# my_ws2812.net
KiCad netlist of a schematic drawn in Altium Designer
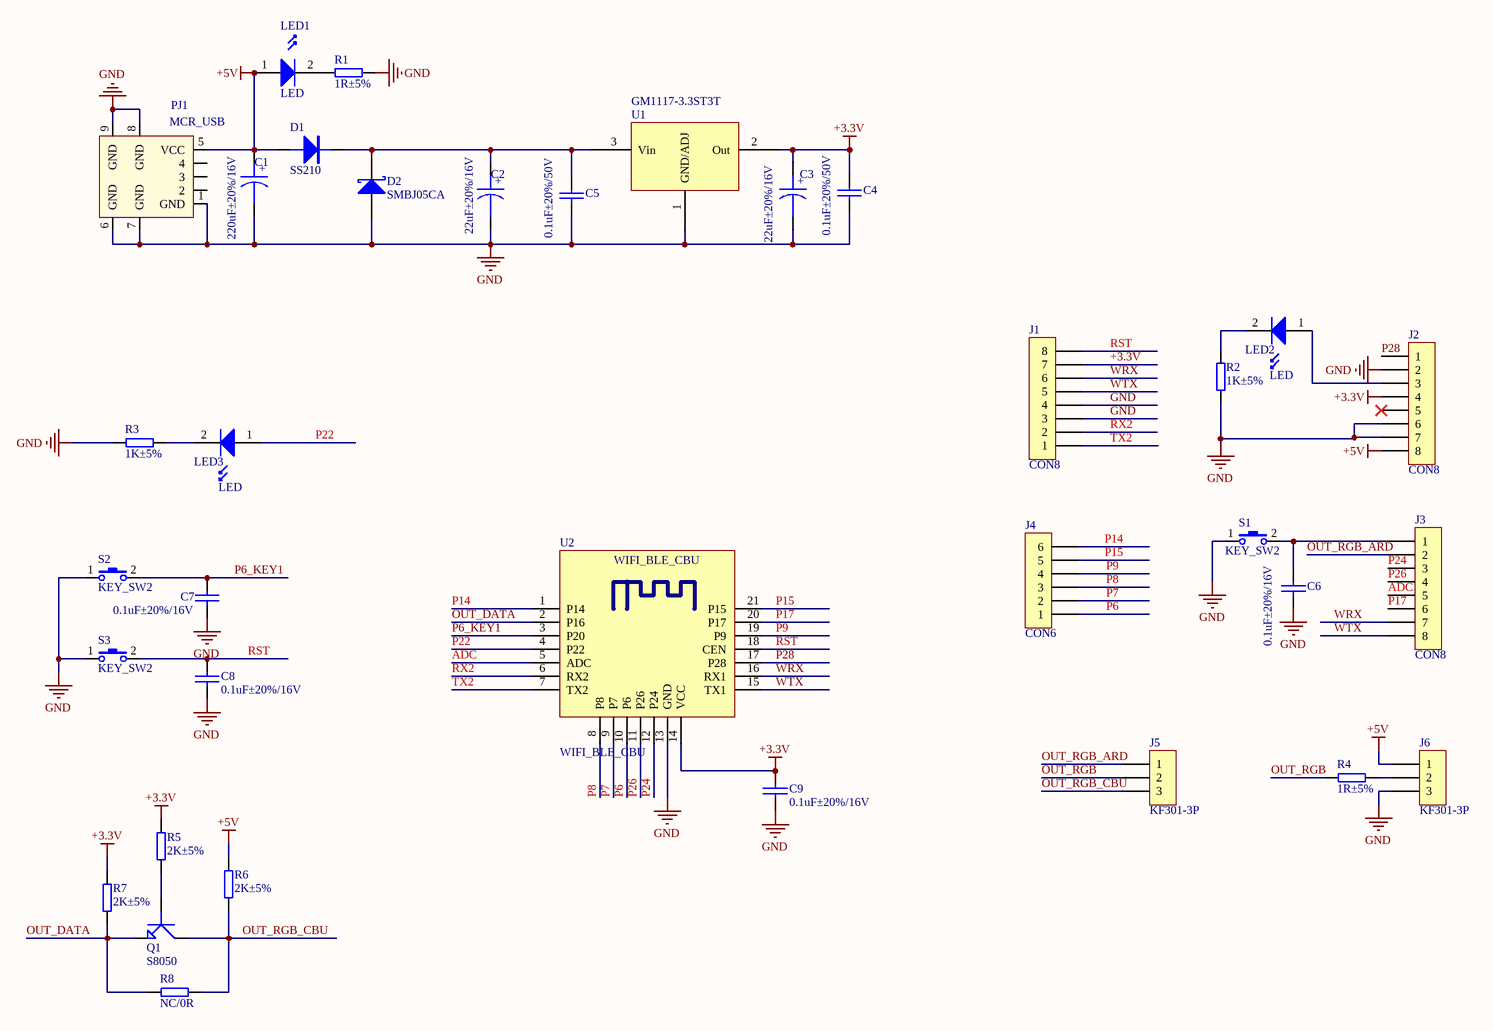
[diagram p0: my_ws2812.SchDoc]

(export (version "E")
  (design (tool "Eeschema 10.0.6"))
  (components
    (comp (ref "C1")
      (value "220uF±20%/16V")
      (footprint "CD0.15")
      (description "Capacitor")
      (libsource (lib "*") (part "CAPACITOR POL"))
    )
    (comp (ref "C2")
      (value "22uF±20%/16V")
      (footprint "钽电容B3528")
      (description "Capacitor")
      (libsource (lib "*") (part "CAPACITOR POL"))
    )
    (comp (ref "C3")
      (value "22uF±20%/16V")
      (footprint "钽电容B3528")
      (description "Capacitor")
      (libsource (lib "*") (part "CAPACITOR POL"))
    )
    (comp (ref "C4")
      (value "0.1uF±20%/50V")
      (footprint "C0603")
      (description "Capacitor")
      (libsource (lib "昊华元件库sch") (part "CAP"))
    )
    (comp (ref "C5")
      (value "0.1uF±20%/50V")
      (footprint "C0603")
      (description "Capacitor")
      (libsource (lib "昊华元件库sch") (part "CAP"))
    )
    (comp (ref "C6")
      (value "0.1uF±20%/16V")
      (footprint "C0603")
      (description "Capacitor")
      (libsource (lib "昊华元件库sch") (part "CAP"))
    )
    (comp (ref "C7")
      (value "0.1uF±20%/16V")
      (footprint "C0603")
      (description "Capacitor")
      (libsource (lib "昊华元件库sch") (part "CAP"))
    )
    (comp (ref "C8")
      (value "0.1uF±20%/16V")
      (footprint "C0603")
      (description "Capacitor")
      (libsource (lib "昊华元件库sch") (part "CAP"))
    )
    (comp (ref "C9")
      (value "0.1uF±20%/16V")
      (footprint "C0603")
      (description "Capacitor")
      (libsource (lib "昊华元件库sch") (part "CAP"))
    )
    (comp (ref "D1")
      (value "SS210")
      (footprint "SMA(DO-214AC)")
      (description "Diode")
      (libsource (lib "小马元件库sch") (part "Diode1"))
    )
    (comp (ref "D2")
      (value "SMBJ05CA")
      (footprint "SMB(DO-214AA)")
      (description "Schottky Diode")
      (fields (field (name "MFR") "Toshiba"))
      (libsource (lib "Miscellaneous Devices") (part "D Schottky"))
    )
    (comp (ref "J1")
      (value "CON8")
      (footprint "HDR1X8Z")
      (description "Connector")
      (libsource (lib "小马元件库sch") (part "CON8"))
    )
    (comp (ref "J2")
      (value "CON8")
      (footprint "HDR1X8Z")
      (description "Connector")
      (libsource (lib "") (part "CON8_1"))
    )
    (comp (ref "J3")
      (value "CON8")
      (footprint "HDR1X8Z")
      (description "Connector")
      (libsource (lib "") (part "CON8_1"))
    )
    (comp (ref "J4")
      (value "CON6")
      (footprint "HDR1X6Z")
      (description "Connector")
      (libsource (lib "小马元件库sch") (part "CON6"))
    )
    (comp (ref "J5")
      (value "KF301-3P")
      (footprint "SIP3 - 2.54")
      (description "Connector")
      (libsource (lib "小马元件库sch") (part "CON3"))
    )
    (comp (ref "J6")
      (value "KF301-3P")
      (footprint "SIP3 - 2.54")
      (description "Connector")
      (libsource (lib "小马元件库sch") (part "CON3"))
    )
    (comp (ref "LED1")
      (value "LED")
      (footprint "LED0805_1")
      (fields (field (name "PUBLISHER") "*"))
      (libsource (lib "小马元件库sch") (part "LED"))
    )
    (comp (ref "LED2")
      (value "LED")
      (footprint "LED0805_1")
      (fields (field (name "PUBLISHER") "*"))
      (libsource (lib "小马元件库sch") (part "LED"))
    )
    (comp (ref "LED3")
      (value "LED")
      (footprint "LED0805_1")
      (fields (field (name "PUBLISHER") "*"))
      (libsource (lib "小马元件库sch") (part "LED"))
    )
    (comp (ref "PJ1")
      (value "MCR_USB")
      (footprint "MICRO_USB-NEW-16.12.12")
      (fields (field (name "PUBLISHER") "*"))
      (libsource (lib "Arduino幻彩灯带") (part "MCR_USB"))
    )
    (comp (ref "Q1")
      (value "S8050")
      (footprint "SOT-23-NPN")
      (description "NPN Transistor")
      (libsource (lib "Arduino幻彩灯带") (part "NPN"))
    )
    (comp (ref "R1") (value "1R±5%") (footprint "R0603") (libsource (lib "昊华元件库sch") (part "RES5")))
    (comp (ref "R2") (value "1K±5%") (footprint "R0603") (libsource (lib "昊华元件库sch") (part "RES5")))
    (comp (ref "R3") (value "1K±5%") (footprint "R0603") (libsource (lib "昊华元件库sch") (part "RES5")))
    (comp (ref "R4") (value "1R±5%") (footprint "R0603") (libsource (lib "昊华元件库sch") (part "RES5")))
    (comp (ref "R5") (value "2K±5%") (footprint "R0603") (libsource (lib "昊华元件库sch") (part "RES5")))
    (comp (ref "R6") (value "2K±5%") (footprint "R0603") (libsource (lib "昊华元件库sch") (part "RES5")))
    (comp (ref "R7") (value "2K±5%") (footprint "R0603") (libsource (lib "昊华元件库sch") (part "RES5")))
    (comp (ref "R8") (value "NC/0R") (footprint "R0603") (libsource (lib "昊华元件库sch") (part "RES5")))
    (comp (ref "S1") (value "KEY_SW2") (footprint "KEY4-SMD") (libsource (lib "小马元件库sch") (part "KEY_SW2")))
    (comp (ref "S2") (value "KEY_SW2") (footprint "KEY4-SMD") (libsource (lib "小马元件库sch") (part "KEY_SW2")))
    (comp (ref "S3") (value "KEY_SW2") (footprint "KEY4-SMD") (libsource (lib "小马元件库sch") (part "KEY_SW2")))
    (comp (ref "U1") (value "GM1117-3.3ST3T") (footprint "SOT-223") (libsource (lib "mylib") (part "GM1117")))
    (comp (ref "U2")
      (value "WIFI_BLE_CBU")
      (footprint "WIFI_BLE_CBU")
      (description "Module")
      (libsource (lib "Arduino幻彩灯带") (part "WIFI_BLE_CBU"))
    )
  )
  (nets
    (net (code "1") (name "+3.3V") (class "Default")
      (node (ref "C3") (pin "1") (pinfunction "1_1") (pintype "passive"))
      (node (ref "C4") (pin "1") (pinfunction "1_1") (pintype "passive"))
      (node (ref "C9") (pin "2") (pinfunction "2_2") (pintype "passive"))
      (node (ref "J1") (pin "7") (pinfunction "7_7") (pintype "passive"))
      (node (ref "J2") (pin "4") (pinfunction "4_4") (pintype "passive"))
      (node (ref "R5") (pin "1") (pinfunction "1_1") (pintype "passive"))
      (node (ref "R7") (pin "1") (pinfunction "1_1") (pintype "passive"))
      (node (ref "U1") (pin "2") (pinfunction "Out_2") (pintype "passive"))
      (node (ref "U2") (pin "14") (pinfunction "VCC_14") (pintype "passive"))
    )
    (net (code "2") (name "+5V") (class "Default")
      (node (ref "C1") (pin "1") (pinfunction "1_1") (pintype "passive"))
      (node (ref "D1") (pin "1") (pinfunction "1_1") (pintype "passive"))
      (node (ref "J2") (pin "8") (pinfunction "8_8") (pintype "passive"))
      (node (ref "J6") (pin "1") (pinfunction "1_1") (pintype "passive"))
      (node (ref "LED1") (pin "1") (pinfunction "1_1") (pintype "passive"))
      (node (ref "PJ1") (pin "5") (pinfunction "VCC_5") (pintype "passive"))
      (node (ref "R6") (pin "1") (pinfunction "1_1") (pintype "passive"))
    )
    (net (code "3") (name "/ADC") (class "Default")
      (node (ref "J3") (pin "5") (pinfunction "5_5") (pintype "passive"))
      (node (ref "U2") (pin "5") (pinfunction "ADC_5") (pintype "passive"))
    )
    (net (code "4") (name "/OUT_DATA") (class "Default")
      (node (ref "Q1") (pin "1") (pinfunction "E_1") (pintype "passive"))
      (node (ref "R7") (pin "2") (pinfunction "2_2") (pintype "passive"))
      (node (ref "R8") (pin "1") (pinfunction "1_1") (pintype "passive"))
      (node (ref "U2") (pin "2") (pinfunction "P16_2") (pintype "passive"))
    )
    (net (code "5") (name "/OUT_RGB") (class "Default")
      (node (ref "J5") (pin "2") (pinfunction "2_2") (pintype "passive"))
      (node (ref "R4") (pin "1") (pinfunction "1_1") (pintype "passive"))
    )
    (net (code "6") (name "/OUT_RGB_ARD") (class "Default")
      (node (ref "J3") (pin "2") (pinfunction "2_2") (pintype "passive"))
      (node (ref "J5") (pin "1") (pinfunction "1_1") (pintype "passive"))
    )
    (net (code "7") (name "/OUT_RGB_CBU") (class "Default")
      (node (ref "J5") (pin "3") (pinfunction "3_3") (pintype "passive"))
      (node (ref "Q1") (pin "3") (pinfunction "C_3") (pintype "passive"))
      (node (ref "R6") (pin "2") (pinfunction "2_2") (pintype "passive"))
      (node (ref "R8") (pin "2") (pinfunction "2_2") (pintype "passive"))
    )
    (net (code "8") (name "/P6") (class "Default")
      (node (ref "J4") (pin "1") (pinfunction "1_1") (pintype "passive"))
      (node (ref "U2") (pin "10") (pinfunction "P6_10") (pintype "passive"))
    )
    (net (code "9") (name "/P6_KEY1") (class "Default")
      (node (ref "C7") (pin "2") (pinfunction "2_2") (pintype "passive"))
      (node (ref "S2") (pin "2") (pinfunction "2_2") (pintype "passive"))
      (node (ref "U2") (pin "3") (pinfunction "P20_3") (pintype "passive"))
    )
    (net (code "10") (name "/P7") (class "Default")
      (node (ref "J4") (pin "2") (pinfunction "2_2") (pintype "passive"))
      (node (ref "U2") (pin "9") (pinfunction "P7_9") (pintype "passive"))
    )
    (net (code "11") (name "/P8") (class "Default")
      (node (ref "J4") (pin "3") (pinfunction "3_3") (pintype "passive"))
      (node (ref "U2") (pin "8") (pinfunction "P8_8") (pintype "passive"))
    )
    (net (code "12") (name "/P9") (class "Default")
      (node (ref "J4") (pin "4") (pinfunction "4_4") (pintype "passive"))
      (node (ref "U2") (pin "19") (pinfunction "P9_19") (pintype "passive"))
    )
    (net (code "13") (name "/P14") (class "Default")
      (node (ref "J4") (pin "6") (pinfunction "6_6") (pintype "passive"))
      (node (ref "U2") (pin "1") (pinfunction "P14_1") (pintype "passive"))
    )
    (net (code "14") (name "/P15") (class "Default")
      (node (ref "J4") (pin "5") (pinfunction "5_5") (pintype "passive"))
      (node (ref "U2") (pin "21") (pinfunction "P15_21") (pintype "passive"))
    )
    (net (code "15") (name "/P17") (class "Default")
      (node (ref "J3") (pin "6") (pinfunction "6_6") (pintype "passive"))
      (node (ref "U2") (pin "20") (pinfunction "P17_20") (pintype "passive"))
    )
    (net (code "16") (name "/P22") (class "Default")
      (node (ref "LED3") (pin "1") (pinfunction "1_1") (pintype "passive"))
      (node (ref "U2") (pin "4") (pinfunction "P22_4") (pintype "passive"))
    )
    (net (code "17") (name "/P24") (class "Default")
      (node (ref "J3") (pin "3") (pinfunction "3_3") (pintype "passive"))
      (node (ref "U2") (pin "12") (pinfunction "P24_12") (pintype "passive"))
    )
    (net (code "18") (name "/P26") (class "Default")
      (node (ref "J3") (pin "4") (pinfunction "4_4") (pintype "passive"))
      (node (ref "U2") (pin "11") (pinfunction "P26_11") (pintype "passive"))
    )
    (net (code "19") (name "/P28") (class "Default")
      (node (ref "J2") (pin "1") (pinfunction "1_1") (pintype "passive"))
      (node (ref "U2") (pin "17") (pinfunction "P28_17") (pintype "passive"))
    )
    (net (code "20") (name "/RST") (class "Default")
      (node (ref "C8") (pin "1") (pinfunction "1_1") (pintype "passive"))
      (node (ref "J1") (pin "8") (pinfunction "8_8") (pintype "passive"))
      (node (ref "S3") (pin "2") (pinfunction "2_2") (pintype "passive"))
      (node (ref "U2") (pin "18") (pinfunction "CEN_18") (pintype "passive"))
    )
    (net (code "21") (name "/RX2") (class "Default")
      (node (ref "J1") (pin "2") (pinfunction "2_2") (pintype "passive"))
      (node (ref "U2") (pin "6") (pinfunction "RX2_6") (pintype "passive"))
    )
    (net (code "22") (name "/TX2") (class "Default")
      (node (ref "J1") (pin "1") (pinfunction "1_1") (pintype "passive"))
      (node (ref "U2") (pin "7") (pinfunction "TX2_7") (pintype "passive"))
    )
    (net (code "23") (name "/WRX") (class "Default")
      (node (ref "J1") (pin "6") (pinfunction "6_6") (pintype "passive"))
      (node (ref "J3") (pin "7") (pinfunction "7_7") (pintype "passive"))
      (node (ref "U2") (pin "16") (pinfunction "RX1_16") (pintype "passive"))
    )
    (net (code "24") (name "/WTX") (class "Default")
      (node (ref "J1") (pin "5") (pinfunction "5_5") (pintype "passive"))
      (node (ref "J3") (pin "8") (pinfunction "8_8") (pintype "passive"))
      (node (ref "U2") (pin "15") (pinfunction "TX1_15") (pintype "passive"))
    )
    (net (code "25") (name "GND") (class "Default")
      (node (ref "C1") (pin "2") (pinfunction "2_2") (pintype "passive"))
      (node (ref "C2") (pin "2") (pinfunction "2_2") (pintype "passive"))
      (node (ref "C3") (pin "2") (pinfunction "2_2") (pintype "passive"))
      (node (ref "C4") (pin "2") (pinfunction "2_2") (pintype "passive"))
      (node (ref "C5") (pin "2") (pinfunction "2_2") (pintype "passive"))
      (node (ref "C6") (pin "1") (pinfunction "1_1") (pintype "passive"))
      (node (ref "C7") (pin "1") (pinfunction "1_1") (pintype "passive"))
      (node (ref "C8") (pin "2") (pinfunction "2_2") (pintype "passive"))
      (node (ref "C9") (pin "1") (pinfunction "1_1") (pintype "passive"))
      (node (ref "D2") (pin "1") (pinfunction "A_1") (pintype "passive"))
      (node (ref "J1") (pin "3") (pinfunction "3_3") (pintype "passive"))
      (node (ref "J1") (pin "4") (pinfunction "4_4") (pintype "passive"))
      (node (ref "J2") (pin "2") (pinfunction "2_2") (pintype "passive"))
      (node (ref "J2") (pin "6") (pinfunction "6_6") (pintype "passive"))
      (node (ref "J2") (pin "7") (pinfunction "7_7") (pintype "passive"))
      (node (ref "J6") (pin "3") (pinfunction "3_3") (pintype "passive"))
      (node (ref "PJ1") (pin "1") (pinfunction "GND_1") (pintype "passive"))
      (node (ref "PJ1") (pin "6") (pinfunction "GND_6") (pintype "passive"))
      (node (ref "PJ1") (pin "7") (pinfunction "GND_7") (pintype "passive"))
      (node (ref "PJ1") (pin "8") (pinfunction "GND_8") (pintype "passive"))
      (node (ref "PJ1") (pin "9") (pinfunction "GND_9") (pintype "passive"))
      (node (ref "R1") (pin "2") (pinfunction "2_2") (pintype "passive"))
      (node (ref "R2") (pin "1") (pinfunction "1_1") (pintype "passive"))
      (node (ref "R3") (pin "2") (pinfunction "2_2") (pintype "passive"))
      (node (ref "S1") (pin "1") (pinfunction "1_1") (pintype "passive"))
      (node (ref "S2") (pin "1") (pinfunction "1_1") (pintype "passive"))
      (node (ref "S3") (pin "1") (pinfunction "1_1") (pintype "passive"))
      (node (ref "U1") (pin "1") (pinfunction "GND/ADJ_1") (pintype "passive"))
      (node (ref "U2") (pin "13") (pinfunction "GND_13") (pintype "passive"))
    )
    (net (code "26") (name "Net-(C6-Pad2)") (class "Default")
      (node (ref "C6") (pin "2") (pinfunction "2_2") (pintype "passive"))
      (node (ref "J3") (pin "1") (pinfunction "1_1") (pintype "passive"))
      (node (ref "S1") (pin "2") (pinfunction "2_2") (pintype "passive"))
    )
    (net (code "27") (name "Net-(D2-K)") (class "Default")
      (node (ref "C2") (pin "1") (pinfunction "1_1") (pintype "passive"))
      (node (ref "C5") (pin "1") (pinfunction "1_1") (pintype "passive"))
      (node (ref "D1") (pin "2") (pinfunction "2_2") (pintype "passive"))
      (node (ref "D2") (pin "2") (pinfunction "K_2") (pintype "passive"))
      (node (ref "U1") (pin "3") (pinfunction "Vin_3") (pintype "passive"))
    )
    (net (code "28") (name "Net-(J2-Pad3)") (class "Default")
      (node (ref "J2") (pin "3") (pinfunction "3_3") (pintype "passive"))
      (node (ref "LED2") (pin "1") (pinfunction "1_1") (pintype "passive"))
    )
    (net (code "29") (name "Net-(J6-Pad2)") (class "Default")
      (node (ref "J6") (pin "2") (pinfunction "2_2") (pintype "passive"))
      (node (ref "R4") (pin "2") (pinfunction "2_2") (pintype "passive"))
    )
    (net (code "30") (name "Net-(LED1-Pad2)") (class "Default")
      (node (ref "LED1") (pin "2") (pinfunction "2_2") (pintype "passive"))
      (node (ref "R1") (pin "1") (pinfunction "1_1") (pintype "passive"))
    )
    (net (code "31") (name "Net-(LED2-Pad2)") (class "Default")
      (node (ref "LED2") (pin "2") (pinfunction "2_2") (pintype "passive"))
      (node (ref "R2") (pin "2") (pinfunction "2_2") (pintype "passive"))
    )
    (net (code "32") (name "Net-(LED3-Pad2)") (class "Default")
      (node (ref "LED3") (pin "2") (pinfunction "2_2") (pintype "passive"))
      (node (ref "R3") (pin "1") (pinfunction "1_1") (pintype "passive"))
    )
    (net (code "33") (name "Net-(Q1-B)") (class "Default")
      (node (ref "Q1") (pin "2") (pinfunction "B_2") (pintype "passive"))
      (node (ref "R5") (pin "2") (pinfunction "2_2") (pintype "passive"))
    )
    (net (code "34") (name "unconnected-(J2-Pad5)") (class "Default")
      (node (ref "J2") (pin "5") (pinfunction "5_5") (pintype "passive+no_connect"))
    )
    (net (code "35") (name "unconnected-(PJ1-Pad2)") (class "Default")
      (node (ref "PJ1") (pin "2") (pinfunction "2_2") (pintype "passive"))
    )
    (net (code "36") (name "unconnected-(PJ1-Pad3)") (class "Default")
      (node (ref "PJ1") (pin "3") (pinfunction "3_3") (pintype "passive"))
    )
    (net (code "37") (name "unconnected-(PJ1-Pad4)") (class "Default")
      (node (ref "PJ1") (pin "4") (pinfunction "4_4") (pintype "passive"))
    )
  )
)
